# POE_V2.net
KiCad netlist of a schematic drawn in EAGLE
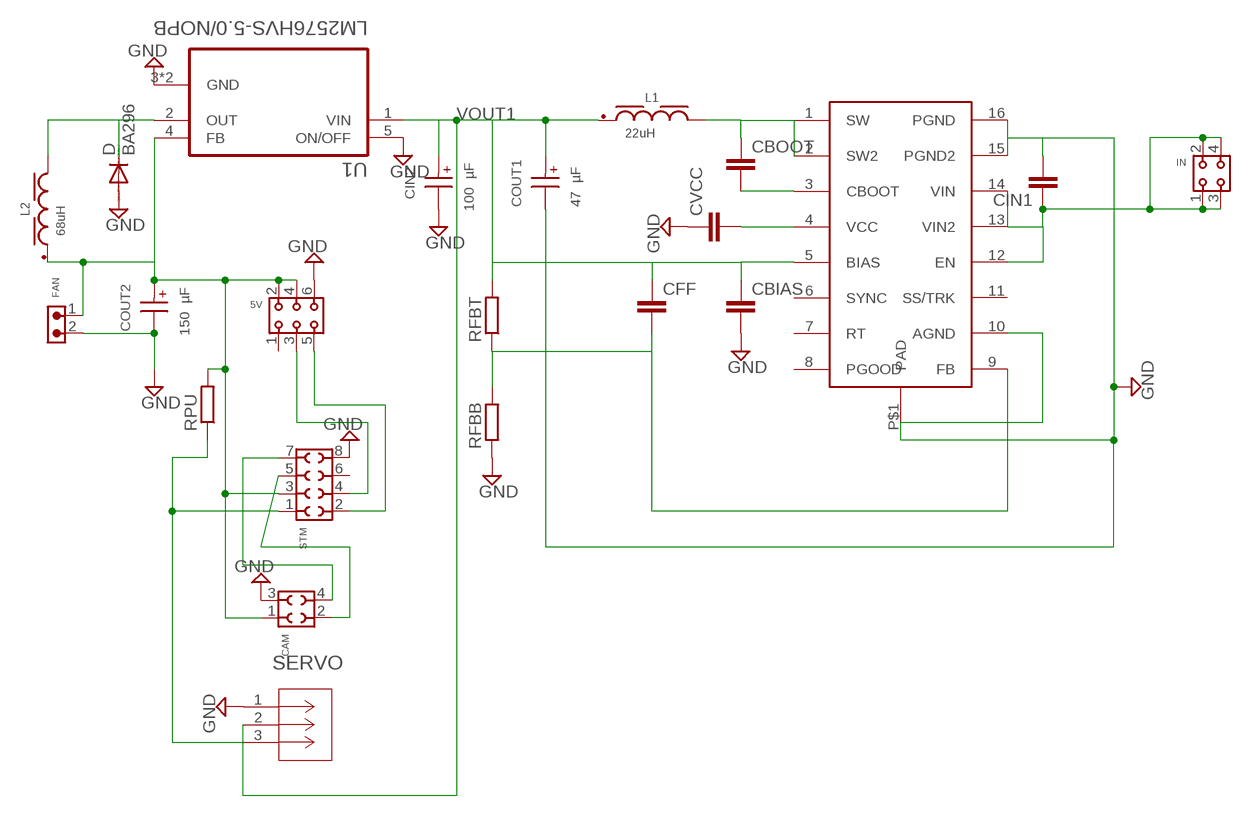
[diagram p0: schematic, sheet 1]

(export (version "E")
  (design (tool "Eeschema 10.0.6"))
  (components
    (comp (ref "5V")
      (value "6130XX21821_61300621821")
      (footprint "eagle-import:61300621821")
      (libsource (lib "eagle-import") (part "6130XX21821_61300621821"))
    )
    (comp (ref "CAM")
      (value "6100XX21821_61000421821")
      (footprint "eagle-import:61000421821")
      (libsource (lib "eagle-import") (part "6100XX21821_61000421821"))
    )
    (comp (ref "CBIAS")
      (value "C-EUC1206")
      (footprint "eagle-import:C1206")
      (libsource (lib "eagle-import") (part "C-EUC1206"))
    )
    (comp (ref "CBOOT")
      (value "C-EUC1206")
      (footprint "eagle-import:C1206")
      (libsource (lib "eagle-import") (part "C-EUC1206"))
    )
    (comp (ref "CFF")
      (value "C-EUC1206")
      (footprint "eagle-import:C1206")
      (libsource (lib "eagle-import") (part "C-EUC1206"))
    )
    (comp (ref "CIN1")
      (value "C-EUC2220K")
      (footprint "eagle-import:C2220K")
      (libsource (lib "eagle-import") (part "rcl_334_C-EUC2220K"))
    )
    (comp (ref "CIN2")
      (value "100 µF")
      (footprint "eagle-import:WCAP-ASLI_6.3X5.5(DXL)")
      (libsource (lib "eagle-import") (part "WCAP-ASLI_6.3X5.5_865080343009"))
    )
    (comp (ref "COUT1")
      (value "47 µF")
      (footprint "eagle-import:WCAP-ASLI_5X5.5(DXL)")
      (libsource (lib "eagle-import") (part "WCAP-ASLI_5X5.5_865080342006"))
    )
    (comp (ref "COUT2")
      (value "150 µF")
      (footprint "eagle-import:WCAP-ASLI_6.3X5.5(DXL)")
      (libsource (lib "eagle-import") (part "WCAP-ASLI_6.3X5.5_865080143008"))
    )
    (comp (ref "CVCC")
      (value "C-EUC1206")
      (footprint "eagle-import:C1206")
      (libsource (lib "eagle-import") (part "C-EUC1206"))
    )
    (comp (ref "D")
      (value "BA296")
      (footprint "eagle-import:P2-15")
      (libsource (lib "eagle-import") (part "BA296"))
    )
    (comp (ref "FAN")
      (value "6130XX11021_61300211021")
      (footprint "eagle-import:61300211021")
      (libsource (lib "eagle-import") (part "6130XX11021_61300211021"))
    )
    (comp (ref "IN")
      (value "6130XX21821_61300421821")
      (footprint "eagle-import:61300421821")
      (libsource (lib "eagle-import") (part "6130XX21821_61300421821"))
    )
    (comp (ref "L1")
      (value "22uH")
      (footprint "eagle-import:WE-PD_1260")
      (libsource (lib "eagle-import") (part "WE-PD_1260_744771122"))
    )
    (comp (ref "L2")
      (value "68uH")
      (footprint "eagle-import:WE-PD_1210")
      (libsource (lib "eagle-import") (part "WE-PD_1210_7447709680"))
    )
    (comp (ref "RFBB")
      (value "R-EU_M1206")
      (footprint "eagle-import:M1206")
      (libsource (lib "eagle-import") (part "R-EU_M1206"))
    )
    (comp (ref "RFBT")
      (value "R-EU_M1206")
      (footprint "eagle-import:M1206")
      (libsource (lib "eagle-import") (part "R-EU_M1206"))
    )
    (comp (ref "RPU")
      (value "R-EU_M1206")
      (footprint "eagle-import:M1206")
      (libsource (lib "eagle-import") (part "R-EU_M1206"))
    )
    (comp (ref "SERVO")
      (value "22035035")
      (footprint "eagle-import:CON_22035035")
      (fields (field (name "COPYRIGHT") "Copyright (C) 2018 Accelerated Designs. All rights reserved"))
      (libsource (lib "eagle-import") (part "22035035"))
    )
    (comp (ref "STM")
      (value "6100XX21821_61000821821")
      (footprint "eagle-import:61000821821")
      (libsource (lib "eagle-import") (part "6100XX21821_61000821821"))
    )
    (comp (ref "U$1")
      (value "LM46002")
      (footprint "eagle-import:TSSOP16")
      (libsource (lib "eagle-import") (part "LM46002"))
    )
    (comp (ref "U1")
      (value "LM2576HVS-5.0/NOPB")
      (footprint "eagle-import:VREG_TPS79625KTTR")
      (fields
        (field (name "DIGI-KEY_PART_NUMBER") "LM2576HVS-5.0/NOPB-ND")
        (field (name "MF") "Texas Instruments")
      )
      (libsource (lib "eagle-import") (part "LM2576HVS-5.0/NOPB"))
    )
  )
  (nets
    (net (code "1") (name "/VOUT1") (class "Default")
      (node (ref "CBIAS") (pin "1") (pinfunction "1_1") (pintype "passive"))
      (node (ref "CFF") (pin "1") (pinfunction "1_1") (pintype "passive"))
      (node (ref "CIN2") (pin "1") (pinfunction "+_1") (pintype "passive"))
      (node (ref "COUT1") (pin "1") (pinfunction "+_1") (pintype "passive"))
      (node (ref "L1") (pin "1") (pinfunction "1_1") (pintype "passive"))
      (node (ref "RFBT") (pin "2") (pinfunction "2_2") (pintype "passive"))
      (node (ref "SERVO") (pin "2") (pinfunction "2_2") (pintype "passive"))
      (node (ref "U$1") (pin "5") (pinfunction "BIAS_5") (pintype "bidirectional"))
      (node (ref "U1") (pin "1") (pinfunction "VIN_1") (pintype "input"))
    )
    (net (code "2") (name "GND") (class "Default")
      (node (ref "5V") (pin "6") (pinfunction "6_6") (pintype "passive"))
      (node (ref "CAM") (pin "3") (pinfunction "3_3") (pintype "passive"))
      (node (ref "CBIAS") (pin "2") (pinfunction "2_2") (pintype "passive"))
      (node (ref "CIN1") (pin "2") (pinfunction "2_2") (pintype "passive"))
      (node (ref "CIN2") (pin "2") (pinfunction "-_2") (pintype "passive"))
      (node (ref "COUT1") (pin "2") (pinfunction "-_2") (pintype "passive"))
      (node (ref "COUT2") (pin "2") (pinfunction "-_2") (pintype "passive"))
      (node (ref "CVCC") (pin "1") (pinfunction "1_1") (pintype "passive"))
      (node (ref "D") (pin "A") (pinfunction "A_A") (pintype "passive"))
      (node (ref "FAN") (pin "2") (pinfunction "2_2") (pintype "passive"))
      (node (ref "RFBB") (pin "1") (pinfunction "1_1") (pintype "passive"))
      (node (ref "SERVO") (pin "1") (pinfunction "1_1") (pintype "passive"))
      (node (ref "STM") (pin "8") (pinfunction "8_8") (pintype "passive"))
      (node (ref "U$1") (pin "10") (pinfunction "AGND_10") (pintype "bidirectional"))
      (node (ref "U$1") (pin "15") (pinfunction "PGND2_15") (pintype "bidirectional"))
      (node (ref "U$1") (pin "16") (pinfunction "PGND_16") (pintype "bidirectional"))
      (node (ref "U$1") (pin "P$1") (pinfunction "PAD_P$1") (pintype "bidirectional"))
      (node (ref "U1") (pin "3") (pinfunction "GND_3") (pintype "power_in"))
      (node (ref "U1") (pin "5") (pinfunction "ON/OFF_5") (pintype "input"))
      (node (ref "U1") (pin "6") (pinfunction "GND_6") (pintype "power_in"))
    )
    (net (code "3") (name "Net-(5V-Pad3)") (class "Default")
      (node (ref "5V") (pin "3") (pinfunction "3_3") (pintype "passive"))
      (node (ref "STM") (pin "4") (pinfunction "4_4") (pintype "passive"))
    )
    (net (code "4") (name "Net-(5V-Pad5)") (class "Default")
      (node (ref "5V") (pin "5") (pinfunction "5_5") (pintype "passive"))
      (node (ref "STM") (pin "2") (pinfunction "2_2") (pintype "passive"))
    )
    (net (code "5") (name "Net-(CAM-Pad2)") (class "Default")
      (node (ref "CAM") (pin "2") (pinfunction "2_2") (pintype "passive"))
      (node (ref "STM") (pin "5") (pinfunction "5_5") (pintype "passive"))
    )
    (net (code "6") (name "Net-(CAM-Pad4)") (class "Default")
      (node (ref "CAM") (pin "4") (pinfunction "4_4") (pintype "passive"))
      (node (ref "STM") (pin "7") (pinfunction "7_7") (pintype "passive"))
    )
    (net (code "7") (name "Net-(COUT2-+)") (class "Default")
      (node (ref "5V") (pin "2") (pinfunction "2_2") (pintype "passive"))
      (node (ref "5V") (pin "4") (pinfunction "4_4") (pintype "passive"))
      (node (ref "CAM") (pin "1") (pinfunction "1_1") (pintype "passive"))
      (node (ref "COUT2") (pin "1") (pinfunction "+_1") (pintype "passive"))
      (node (ref "FAN") (pin "1") (pinfunction "1_1") (pintype "passive"))
      (node (ref "L2") (pin "1") (pinfunction "1_1") (pintype "passive"))
      (node (ref "RPU") (pin "2") (pinfunction "2_2") (pintype "passive"))
      (node (ref "STM") (pin "3") (pinfunction "3_3") (pintype "passive"))
      (node (ref "U1") (pin "4") (pinfunction "FB_4") (pintype "output"))
    )
    (net (code "8") (name "Net-(RPU-Pad1)") (class "Default")
      (node (ref "RPU") (pin "1") (pinfunction "1_1") (pintype "passive"))
      (node (ref "SERVO") (pin "3") (pinfunction "3_3") (pintype "passive"))
      (node (ref "STM") (pin "1") (pinfunction "1_1") (pintype "passive"))
    )
    (net (code "9") (name "Net-(U$1-CBOOT)") (class "Default")
      (node (ref "CBOOT") (pin "2") (pinfunction "2_2") (pintype "passive"))
      (node (ref "U$1") (pin "3") (pinfunction "CBOOT_3") (pintype "bidirectional"))
    )
    (net (code "10") (name "Net-(U$1-EN)") (class "Default")
      (node (ref "CIN1") (pin "1") (pinfunction "1_1") (pintype "passive"))
      (node (ref "IN") (pin "1") (pinfunction "1_1") (pintype "passive"))
      (node (ref "IN") (pin "2") (pinfunction "2_2") (pintype "passive"))
      (node (ref "IN") (pin "3") (pinfunction "3_3") (pintype "passive"))
      (node (ref "IN") (pin "4") (pinfunction "4_4") (pintype "passive"))
      (node (ref "U$1") (pin "12") (pinfunction "EN_12") (pintype "bidirectional"))
      (node (ref "U$1") (pin "13") (pinfunction "VIN2_13") (pintype "bidirectional"))
      (node (ref "U$1") (pin "14") (pinfunction "VIN_14") (pintype "bidirectional"))
    )
    (net (code "11") (name "Net-(U$1-FB)") (class "Default")
      (node (ref "CFF") (pin "2") (pinfunction "2_2") (pintype "passive"))
      (node (ref "RFBB") (pin "2") (pinfunction "2_2") (pintype "passive"))
      (node (ref "RFBT") (pin "1") (pinfunction "1_1") (pintype "passive"))
      (node (ref "U$1") (pin "9") (pinfunction "FB_9") (pintype "bidirectional"))
    )
    (net (code "12") (name "Net-(U$1-SW)") (class "Default")
      (node (ref "CBOOT") (pin "1") (pinfunction "1_1") (pintype "passive"))
      (node (ref "L1") (pin "2") (pinfunction "2_2") (pintype "passive"))
      (node (ref "U$1") (pin "1") (pinfunction "SW_1") (pintype "bidirectional"))
      (node (ref "U$1") (pin "2") (pinfunction "SW2_2") (pintype "bidirectional"))
    )
    (net (code "13") (name "Net-(U$1-VCC)") (class "Default")
      (node (ref "CVCC") (pin "2") (pinfunction "2_2") (pintype "passive"))
      (node (ref "U$1") (pin "4") (pinfunction "VCC_4") (pintype "bidirectional"))
    )
    (net (code "14") (name "Net-(U1-OUT)") (class "Default")
      (node (ref "D") (pin "C") (pinfunction "C_C") (pintype "passive"))
      (node (ref "L2") (pin "2") (pinfunction "2_2") (pintype "passive"))
      (node (ref "U1") (pin "2") (pinfunction "OUT_2") (pintype "output"))
    )
    (net (code "15") (name "unconnected-(5V-Pad1)") (class "Default")
      (node (ref "5V") (pin "1") (pinfunction "1_1") (pintype "passive"))
    )
    (net (code "16") (name "unconnected-(STM-Pad6)") (class "Default")
      (node (ref "STM") (pin "6") (pinfunction "6_6") (pintype "passive"))
    )
    (net (code "17") (name "unconnected-(U$1-PGOOD-Pad8)") (class "Default")
      (node (ref "U$1") (pin "8") (pinfunction "PGOOD_8") (pintype "bidirectional"))
    )
    (net (code "18") (name "unconnected-(U$1-RT-Pad7)") (class "Default")
      (node (ref "U$1") (pin "7") (pinfunction "RT_7") (pintype "bidirectional"))
    )
    (net (code "19") (name "unconnected-(U$1-SS{slash}TRK-Pad11)") (class "Default")
      (node (ref "U$1") (pin "11") (pinfunction "SS/TRK_11") (pintype "bidirectional"))
    )
    (net (code "20") (name "unconnected-(U$1-SYNC-Pad6)") (class "Default")
      (node (ref "U$1") (pin "6") (pinfunction "SYNC_6") (pintype "bidirectional"))
    )
  )
)
